# eBOOK_v32.net
KiCad netlist of a schematic drawn in EAGLE
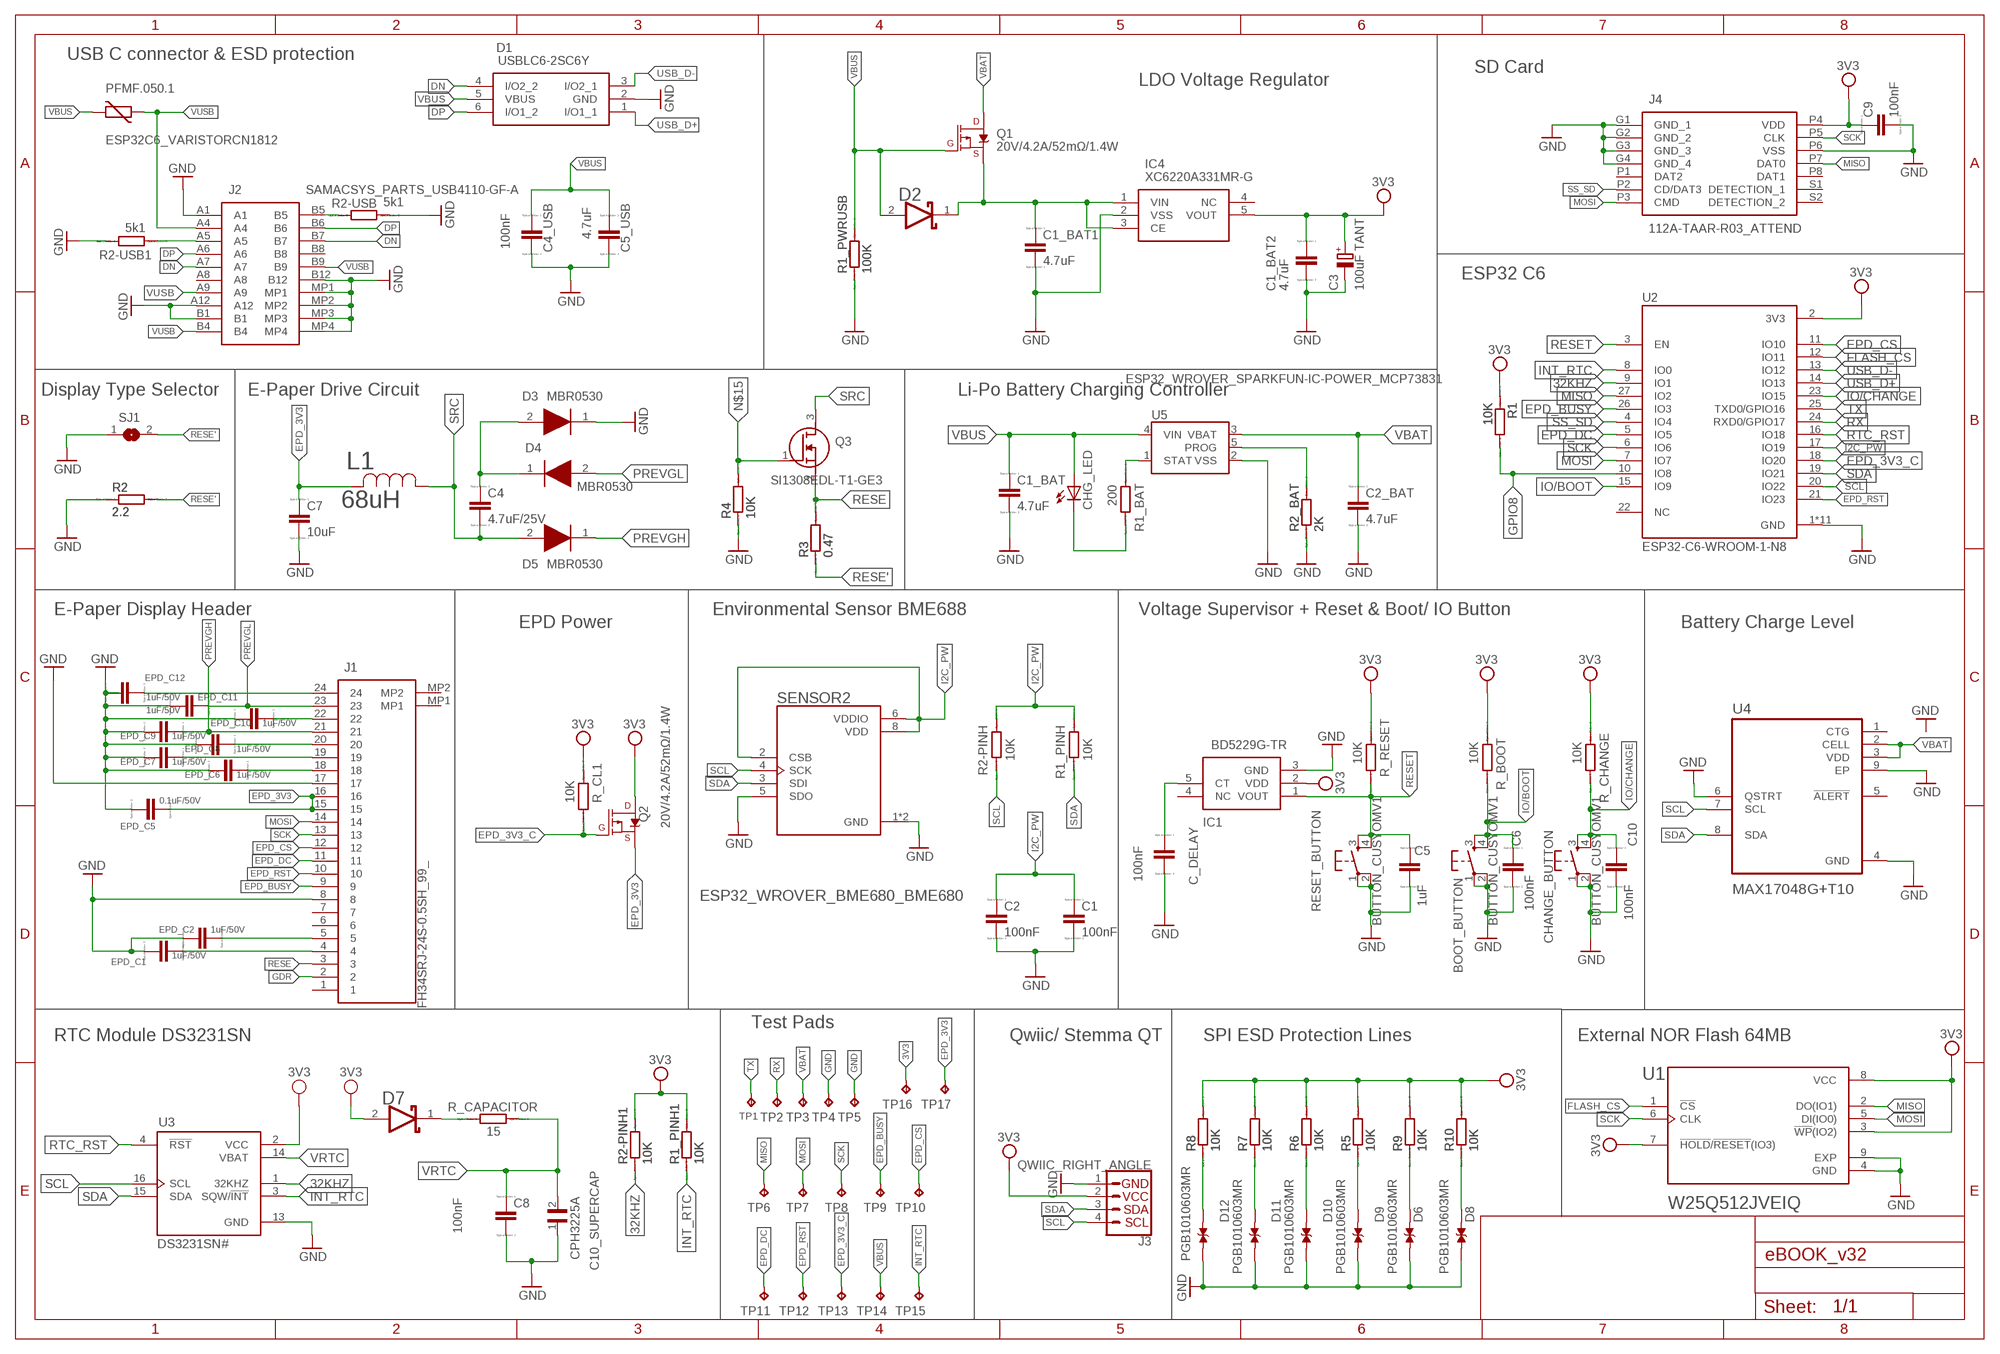
[diagram p0: schematic, sheet 1]

(export (version "E")
  (design (tool "Eeschema 10.0.6"))
  (components
    (comp (ref "BOOT_BUTTON")
      (value "BUTTON_CUSYOMV1")
      (footprint "eagle-import:MYBUTTON")
      (libsource (lib "eagle-import") (part "BUTTON_CUSYOMV1"))
    )
    (comp (ref "C1")
      (value "100nF")
      (footprint "eagle-import:ESP32_WROVER_EAGLE-LTSPICE_C0402")
      (libsource (lib "eagle-import") (part "ESP32_WROVER_EAGLE-LTSPICE_CC0402"))
    )
    (comp (ref "C1_BAT")
      (value "4.7uF")
      (footprint "eagle-import:ESP32_WROVER_EAGLE-LTSPICE_C0402")
      (libsource (lib "eagle-import") (part "ESP32_WROVER_EAGLE-LTSPICE_CC0402"))
    )
    (comp (ref "C1_BAT1")
      (value "4.7uF")
      (footprint "eagle-import:ESP32_WROVER_EAGLE-LTSPICE_C0402")
      (libsource (lib "eagle-import") (part "ESP32_WROVER_EAGLE-LTSPICE_CC0402"))
    )
    (comp (ref "C1_BAT2")
      (value "4.7uF")
      (footprint "eagle-import:ESP32_WROVER_EAGLE-LTSPICE_C0402")
      (libsource (lib "eagle-import") (part "ESP32_WROVER_EAGLE-LTSPICE_CC0402"))
    )
    (comp (ref "C2")
      (value "100nF")
      (footprint "eagle-import:ESP32_WROVER_EAGLE-LTSPICE_C0402")
      (libsource (lib "eagle-import") (part "ESP32_WROVER_EAGLE-LTSPICE_CC0402"))
    )
    (comp (ref "C2_BAT")
      (value "4.7uF")
      (footprint "eagle-import:ESP32_WROVER_EAGLE-LTSPICE_C0402")
      (libsource (lib "eagle-import") (part "ESP32_WROVER_EAGLE-LTSPICE_CC0402"))
    )
    (comp (ref "C3")
      (value "100uF TANT")
      (footprint "eagle-import:RCL_CT3528")
      (libsource (lib "eagle-import") (part "RCL_CPOL-EUCT3528"))
    )
    (comp (ref "C4")
      (value "4.7uF/25V")
      (footprint "eagle-import:ESP32_WROVER_EAGLE-LTSPICE_C0402")
      (libsource (lib "eagle-import") (part "ESP32_WROVER_EAGLE-LTSPICE_CC0402"))
    )
    (comp (ref "C4_USB")
      (value "100nF")
      (footprint "eagle-import:ESP32_WROVER_EAGLE-LTSPICE_C0402")
      (libsource (lib "eagle-import") (part "ESP32_WROVER_EAGLE-LTSPICE_CC0402"))
    )
    (comp (ref "C5")
      (value "1uF")
      (footprint "eagle-import:ESP32_WROVER_EAGLE-LTSPICE_C0402")
      (libsource (lib "eagle-import") (part "ESP32_WROVER_EAGLE-LTSPICE_CC0402"))
    )
    (comp (ref "C5_USB")
      (value "4.7uF")
      (footprint "eagle-import:ESP32_WROVER_EAGLE-LTSPICE_C0402")
      (libsource (lib "eagle-import") (part "ESP32_WROVER_EAGLE-LTSPICE_CC0402"))
    )
    (comp (ref "C6")
      (value "100nF")
      (footprint "eagle-import:ESP32_WROVER_EAGLE-LTSPICE_C0402")
      (libsource (lib "eagle-import") (part "ESP32_WROVER_EAGLE-LTSPICE_CC0402"))
    )
    (comp (ref "C7")
      (value "10uF")
      (footprint "eagle-import:ESP32_WROVER_EAGLE-LTSPICE_C0402")
      (libsource (lib "eagle-import") (part "ESP32_WROVER_EAGLE-LTSPICE_CC0402"))
    )
    (comp (ref "C8")
      (value "100nF")
      (footprint "eagle-import:ESP32_WROVER_EAGLE-LTSPICE_C0402")
      (libsource (lib "eagle-import") (part "ESP32_WROVER_EAGLE-LTSPICE_CC0402"))
    )
    (comp (ref "C9")
      (value "100nF")
      (footprint "eagle-import:ESP32_WROVER_EAGLE-LTSPICE_C0402")
      (libsource (lib "eagle-import") (part "ESP32_WROVER_EAGLE-LTSPICE_CC0402"))
    )
    (comp (ref "C10")
      (value "100nF")
      (footprint "eagle-import:ESP32_WROVER_EAGLE-LTSPICE_C0402")
      (libsource (lib "eagle-import") (part "ESP32_WROVER_EAGLE-LTSPICE_CC0402"))
    )
    (comp (ref "C10_SUPERCAP")
      (value "CPH3225A")
      (footprint "eagle-import:CAPCP3225X100N")
      (fields (field (name "MF") "Seiko Instruments"))
      (libsource (lib "eagle-import") (part "CPH3225A"))
    )
    (comp (ref "CHANGE_BUTTON")
      (value "BUTTON_CUSYOMV1")
      (footprint "eagle-import:MYBUTTON")
      (libsource (lib "eagle-import") (part "BUTTON_CUSYOMV1"))
    )
    (comp (ref "CHG_LED")
      (value "ADAFRUIT_LEDCHIP-LED0603")
      (footprint "eagle-import:ADAFRUIT_CHIP-LED0603")
      (libsource (lib "eagle-import") (part "ADAFRUIT_LEDCHIP-LED0603"))
    )
    (comp (ref "C_DELAY")
      (value "100nF")
      (footprint "eagle-import:ESP32_WROVER_EAGLE-LTSPICE_C0402")
      (libsource (lib "eagle-import") (part "ESP32_WROVER_EAGLE-LTSPICE_CC0402"))
    )
    (comp (ref "D1")
      (value "USBLC6-2SC6Y")
      (footprint "eagle-import:SOT95P280X145-6N")
      (fields (field (name "MF") "STMicroelectronics"))
      (libsource (lib "eagle-import") (part "USBLC6-2SC6Y"))
    )
    (comp (ref "D2")
      (value "ESP32_WROVER_AVX---SD0805S020S1R0_AVX_SD0805S020S1R0_0_0AVX_SD0805S020S1R0_0_0")
      (footprint "eagle-import:ESP32_WROVER_AVX---SD0805S020S1R0_AVX_SD0805S020S1R0_0")
      (fields
        (field (name "DIGIKEY_PART_NUMBER") "478-7800-1-ND")
        (field (name "MF") "AVX")
        (field (name "MOUSER_PART_NUMBER") "581-SD0805S020S1R0")
      )
      (libsource (lib "eagle-import") (part "ESP32_WROVER_AVX---SD0805S020S1R0_AVX_SD0805S020S1R0_0_0AVX_SD0805S020S1R0_0_0"))
    )
    (comp (ref "D3")
      (value "MBR0530")
      (footprint "eagle-import:SOD3716X135N")
      (fields (field (name "MF") "ON Semiconductor"))
      (libsource (lib "eagle-import") (part "MBR0530"))
    )
    (comp (ref "D4")
      (value "MBR0530")
      (footprint "eagle-import:SOD3716X135N")
      (fields (field (name "MF") "ON Semiconductor"))
      (libsource (lib "eagle-import") (part "MBR0530"))
    )
    (comp (ref "D5")
      (value "MBR0530")
      (footprint "eagle-import:SOD3716X135N")
      (fields (field (name "MF") "ON Semiconductor"))
      (libsource (lib "eagle-import") (part "MBR0530"))
    )
    (comp (ref "D6")
      (value "PGB1010603MR")
      (footprint "eagle-import:DIOC1608X36N")
      (fields (field (name "MF") "Littelfuse Inc."))
      (libsource (lib "eagle-import") (part "PGB1010603MR"))
    )
    (comp (ref "D7")
      (value "ESP32_WROVER_AVX---SD0805S020S1R0_AVX_SD0805S020S1R0_0_0AVX_SD0805S020S1R0_0_0")
      (footprint "eagle-import:ESP32_WROVER_AVX---SD0805S020S1R0_AVX_SD0805S020S1R0_0")
      (fields
        (field (name "DIGIKEY_PART_NUMBER") "478-7800-1-ND")
        (field (name "MF") "AVX")
        (field (name "MOUSER_PART_NUMBER") "581-SD0805S020S1R0")
      )
      (libsource (lib "eagle-import") (part "ESP32_WROVER_AVX---SD0805S020S1R0_AVX_SD0805S020S1R0_0_0AVX_SD0805S020S1R0_0_0"))
    )
    (comp (ref "D8")
      (value "PGB1010603MR")
      (footprint "eagle-import:DIOC1608X36N")
      (fields (field (name "MF") "Littelfuse Inc."))
      (libsource (lib "eagle-import") (part "PGB1010603MR"))
    )
    (comp (ref "D9")
      (value "PGB1010603MR")
      (footprint "eagle-import:DIOC1608X36N")
      (fields (field (name "MF") "Littelfuse Inc."))
      (libsource (lib "eagle-import") (part "PGB1010603MR"))
    )
    (comp (ref "D10")
      (value "PGB1010603MR")
      (footprint "eagle-import:DIOC1608X36N")
      (fields (field (name "MF") "Littelfuse Inc."))
      (libsource (lib "eagle-import") (part "PGB1010603MR"))
    )
    (comp (ref "D11")
      (value "PGB1010603MR")
      (footprint "eagle-import:DIOC1608X36N")
      (fields (field (name "MF") "Littelfuse Inc."))
      (libsource (lib "eagle-import") (part "PGB1010603MR"))
    )
    (comp (ref "D12")
      (value "PGB1010603MR")
      (footprint "eagle-import:DIOC1608X36N")
      (fields (field (name "MF") "Littelfuse Inc."))
      (libsource (lib "eagle-import") (part "PGB1010603MR"))
    )
    (comp (ref "EPD_C1")
      (value "1uF/50V")
      (footprint "eagle-import:ESP32_WROVER_EAGLE-LTSPICE_C0402")
      (libsource (lib "eagle-import") (part "ESP32_WROVER_EAGLE-LTSPICE_CC0402"))
    )
    (comp (ref "EPD_C2")
      (value "1uF/50V")
      (footprint "eagle-import:ESP32_WROVER_EAGLE-LTSPICE_C0402")
      (libsource (lib "eagle-import") (part "ESP32_WROVER_EAGLE-LTSPICE_CC0402"))
    )
    (comp (ref "EPD_C5")
      (value "0.1uF/50V")
      (footprint "eagle-import:ESP32_WROVER_EAGLE-LTSPICE_C0402")
      (libsource (lib "eagle-import") (part "ESP32_WROVER_EAGLE-LTSPICE_CC0402"))
    )
    (comp (ref "EPD_C6")
      (value "1uF/50V")
      (footprint "eagle-import:ESP32_WROVER_EAGLE-LTSPICE_C0402")
      (libsource (lib "eagle-import") (part "ESP32_WROVER_EAGLE-LTSPICE_CC0402"))
    )
    (comp (ref "EPD_C7")
      (value "1uF/50V")
      (footprint "eagle-import:ESP32_WROVER_EAGLE-LTSPICE_C0402")
      (libsource (lib "eagle-import") (part "ESP32_WROVER_EAGLE-LTSPICE_CC0402"))
    )
    (comp (ref "EPD_C8")
      (value "1uF/50V")
      (footprint "eagle-import:ESP32_WROVER_EAGLE-LTSPICE_C0402")
      (libsource (lib "eagle-import") (part "ESP32_WROVER_EAGLE-LTSPICE_CC0402"))
    )
    (comp (ref "EPD_C9")
      (value "1uF/50V")
      (footprint "eagle-import:ESP32_WROVER_EAGLE-LTSPICE_C0402")
      (libsource (lib "eagle-import") (part "ESP32_WROVER_EAGLE-LTSPICE_CC0402"))
    )
    (comp (ref "EPD_C10")
      (value "1uF/50V")
      (footprint "eagle-import:ESP32_WROVER_EAGLE-LTSPICE_C0402")
      (libsource (lib "eagle-import") (part "ESP32_WROVER_EAGLE-LTSPICE_CC0402"))
    )
    (comp (ref "EPD_C11")
      (value "1uF/50V")
      (footprint "eagle-import:ESP32_WROVER_EAGLE-LTSPICE_C0402")
      (libsource (lib "eagle-import") (part "ESP32_WROVER_EAGLE-LTSPICE_CC0402"))
    )
    (comp (ref "EPD_C12")
      (value "1uF/50V")
      (footprint "eagle-import:ESP32_WROVER_EAGLE-LTSPICE_C0402")
      (libsource (lib "eagle-import") (part "ESP32_WROVER_EAGLE-LTSPICE_CC0402"))
    )
    (comp (ref "IC1")
      (value "BD5229G-TR")
      (footprint "eagle-import:SOT95P280X125-5N")
      (fields (field (name "MOUSER_PART_NUMBER") "755-BD5229G-TR"))
      (libsource (lib "eagle-import") (part "BD5229G-TR"))
    )
    (comp (ref "IC4")
      (value "XC6220A331MR-G")
      (footprint "eagle-import:SOT95P280X120-5N")
      (fields (field (name "MOUSER_PART_NUMBER") "865-XC6220A331MR-G"))
      (libsource (lib "eagle-import") (part "XC6220A331MR-G"))
    )
    (comp (ref "J1")
      (value "FH34SRJ-24S-0.5SH_99_")
      (footprint "eagle-import:FH34SRJ24S05SH99")
      (fields
        (field (name "MANUFACTURER_PART_NUMBER") "FH34SRJ-24S-0.5SH(99)")
        (field (name "MOUSER_PART_NUMBER") "798-FH34SRJ24S05SH99")
      )
      (libsource (lib "eagle-import") (part "FH34SRJ-24S-0.5SH_99_"))
    )
    (comp (ref "J2")
      (value "SAMACSYS_PARTS_USB4110-GF-A")
      (footprint "eagle-import:SAMACSYS_PARTS_USB4110GFA")
      (fields
        (field (name "MANUFACTURER_PART_NUMBER") "USB4110-GF-A")
        (field (name "MOUSER_PART_NUMBER") "640-USB4110-GF-A")
      )
      (libsource (lib "eagle-import") (part "SAMACSYS_PARTS_USB4110-GF-A"))
    )
    (comp (ref "J3")
      (value "QWIIC_RIGHT_ANGLE")
      (footprint "eagle-import:JST04_1MM_RA")
      (libsource (lib "eagle-import") (part "QWIIC_CONNECTORJS-1MM"))
    )
    (comp (ref "J4")
      (value "112A-TAAR-R03_ATTEND")
      (footprint "eagle-import:112ATAARR03ATTEND")
      (fields (field (name "MANUFACTURER_PART_NUMBER") "112A-TAAR-R03 ATTEND"))
      (libsource (lib "eagle-import") (part "112A-TAAR-R03_ATTEND"))
    )
    (comp (ref "L1")
      (value "68uH")
      (footprint "eagle-import:IND_4828-WE-TPC_WRE")
      (fields
        (field (name "MANUFACTURER_PART_NUMBER") "744043680")
        (field (name "COPYRIGHT") "Copyright (C) 2024 Ultra Librarian. All rights reserved.")
      )
      (libsource (lib "eagle-import") (part "744043680IND_4828-WE-TPC_WRE"))
    )
    (comp (ref "PFMF.050.1")
      (value "ESP32C6_VARISTORCN1812")
      (footprint "eagle-import:ESP32C6_VARISTOR_CT_CN1812")
      (libsource (lib "eagle-import") (part "ESP32C6_VARISTORCN1812"))
    )
    (comp (ref "Q1")
      (value "20V/4.2A/52mΩ/1.4W")
      (footprint "eagle-import:ESP32_WROVER_SPARKFUN-DISCRETESEMI_SOT23-3")
      (libsource (lib "eagle-import") (part "ESP32_WROVER_SPARKFUN-DISCRETESEMI_MOSFET_PCH-DMG2305UX-7"))
    )
    (comp (ref "Q2")
      (value "20V/4.2A/52mΩ/1.4W")
      (footprint "eagle-import:ESP32_WROVER_SPARKFUN-DISCRETESEMI_SOT23-3")
      (libsource (lib "eagle-import") (part "ESP32_WROVER_SPARKFUN-DISCRETESEMI_MOSFET_PCH-DMG2305UX-7"))
    )
    (comp (ref "Q3")
      (value "SI1308EDL-T1-GE3")
      (footprint "eagle-import:SOT65P210X110-3N")
      (fields (field (name "MF") "Vishay Siliconix"))
      (libsource (lib "eagle-import") (part "SI1308EDL-T1-GE3"))
    )
    (comp (ref "R1")
      (value "10K")
      (footprint "eagle-import:ESP32_WROVER_EAGLE-LTSPICE_R0402")
      (libsource (lib "eagle-import") (part "ESP32_WROVER_EAGLE-LTSPICE_RR0402"))
    )
    (comp (ref "R1_BAT")
      (value "200")
      (footprint "eagle-import:ESP32_WROVER_EAGLE-LTSPICE_R0402")
      (libsource (lib "eagle-import") (part "ESP32_WROVER_EAGLE-LTSPICE_RR0402"))
    )
    (comp (ref "R1_PINH")
      (value "10K")
      (footprint "eagle-import:ESP32_WROVER_EAGLE-LTSPICE_R0402")
      (libsource (lib "eagle-import") (part "ESP32_WROVER_EAGLE-LTSPICE_RR0402"))
    )
    (comp (ref "R1_PINH1")
      (value "10K")
      (footprint "eagle-import:ESP32_WROVER_EAGLE-LTSPICE_R0402")
      (libsource (lib "eagle-import") (part "ESP32_WROVER_EAGLE-LTSPICE_RR0402"))
    )
    (comp (ref "R1_PWRUSB")
      (value "100K")
      (footprint "eagle-import:ESP32_WROVER_EAGLE-LTSPICE_R0402")
      (libsource (lib "eagle-import") (part "ESP32_WROVER_EAGLE-LTSPICE_RR0402"))
    )
    (comp (ref "R2")
      (value "2.2")
      (footprint "eagle-import:ESP32_WROVER_EAGLE-LTSPICE_R0402")
      (libsource (lib "eagle-import") (part "ESP32_WROVER_EAGLE-LTSPICE_RR0402"))
    )
    (comp (ref "R2-PINH")
      (value "10K")
      (footprint "eagle-import:ESP32_WROVER_EAGLE-LTSPICE_R0402")
      (libsource (lib "eagle-import") (part "ESP32_WROVER_EAGLE-LTSPICE_RR0402"))
    )
    (comp (ref "R2-PINH1")
      (value "10K")
      (footprint "eagle-import:ESP32_WROVER_EAGLE-LTSPICE_R0402")
      (libsource (lib "eagle-import") (part "ESP32_WROVER_EAGLE-LTSPICE_RR0402"))
    )
    (comp (ref "R2-USB")
      (value "5k1")
      (footprint "eagle-import:ESP32_WROVER_EAGLE-LTSPICE_R0402")
      (libsource (lib "eagle-import") (part "ESP32_WROVER_EAGLE-LTSPICE_RR0402"))
    )
    (comp (ref "R2-USB1")
      (value "5k1")
      (footprint "eagle-import:ESP32_WROVER_EAGLE-LTSPICE_R0402")
      (libsource (lib "eagle-import") (part "ESP32_WROVER_EAGLE-LTSPICE_RR0402"))
    )
    (comp (ref "R2_BAT")
      (value "2K")
      (footprint "eagle-import:ESP32_WROVER_EAGLE-LTSPICE_R0402")
      (libsource (lib "eagle-import") (part "ESP32_WROVER_EAGLE-LTSPICE_RR0402"))
    )
    (comp (ref "R3")
      (value "0.47")
      (footprint "eagle-import:ESP32_WROVER_EAGLE-LTSPICE_R0402")
      (libsource (lib "eagle-import") (part "ESP32_WROVER_EAGLE-LTSPICE_RR0402"))
    )
    (comp (ref "R4")
      (value "10K")
      (footprint "eagle-import:ESP32_WROVER_EAGLE-LTSPICE_R0402")
      (libsource (lib "eagle-import") (part "ESP32_WROVER_EAGLE-LTSPICE_RR0402"))
    )
    (comp (ref "R5")
      (value "10K")
      (footprint "eagle-import:ESP32_WROVER_EAGLE-LTSPICE_R0402")
      (libsource (lib "eagle-import") (part "ESP32_WROVER_EAGLE-LTSPICE_RR0402"))
    )
    (comp (ref "R6")
      (value "10K")
      (footprint "eagle-import:ESP32_WROVER_EAGLE-LTSPICE_R0402")
      (libsource (lib "eagle-import") (part "ESP32_WROVER_EAGLE-LTSPICE_RR0402"))
    )
    (comp (ref "R7")
      (value "10K")
      (footprint "eagle-import:ESP32_WROVER_EAGLE-LTSPICE_R0402")
      (libsource (lib "eagle-import") (part "ESP32_WROVER_EAGLE-LTSPICE_RR0402"))
    )
    (comp (ref "R8")
      (value "10K")
      (footprint "eagle-import:ESP32_WROVER_EAGLE-LTSPICE_R0402")
      (libsource (lib "eagle-import") (part "ESP32_WROVER_EAGLE-LTSPICE_RR0402"))
    )
    (comp (ref "R9")
      (value "10K")
      (footprint "eagle-import:ESP32_WROVER_EAGLE-LTSPICE_R0402")
      (libsource (lib "eagle-import") (part "ESP32_WROVER_EAGLE-LTSPICE_RR0402"))
    )
    (comp (ref "R10")
      (value "10K")
      (footprint "eagle-import:ESP32_WROVER_EAGLE-LTSPICE_R0402")
      (libsource (lib "eagle-import") (part "ESP32_WROVER_EAGLE-LTSPICE_RR0402"))
    )
    (comp (ref "RESET_BUTTON")
      (value "BUTTON_CUSYOMV1")
      (footprint "eagle-import:MYBUTTON")
      (libsource (lib "eagle-import") (part "BUTTON_CUSYOMV1"))
    )
    (comp (ref "R_BOOT")
      (value "10K")
      (footprint "eagle-import:ESP32_WROVER_EAGLE-LTSPICE_R0402")
      (libsource (lib "eagle-import") (part "ESP32_WROVER_EAGLE-LTSPICE_RR0402"))
    )
    (comp (ref "R_CAPACITOR")
      (value "15")
      (footprint "eagle-import:ESP32_WROVER_EAGLE-LTSPICE_R0402")
      (libsource (lib "eagle-import") (part "ESP32_WROVER_EAGLE-LTSPICE_RR0402"))
    )
    (comp (ref "R_CHANGE")
      (value "10K")
      (footprint "eagle-import:ESP32_WROVER_EAGLE-LTSPICE_R0402")
      (libsource (lib "eagle-import") (part "ESP32_WROVER_EAGLE-LTSPICE_RR0402"))
    )
    (comp (ref "R_CL1")
      (value "10K")
      (footprint "eagle-import:ESP32_WROVER_EAGLE-LTSPICE_R0402")
      (libsource (lib "eagle-import") (part "ESP32_WROVER_EAGLE-LTSPICE_RR0402"))
    )
    (comp (ref "R_RESET")
      (value "10K")
      (footprint "eagle-import:ESP32_WROVER_EAGLE-LTSPICE_R0402")
      (libsource (lib "eagle-import") (part "ESP32_WROVER_EAGLE-LTSPICE_RR0402"))
    )
    (comp (ref "SENSOR2")
      (value "ESP32_WROVER_BME680_BME680")
      (footprint "eagle-import:ESP32_WROVER_BME680_PSON80P300X300X100-8N")
      (fields (field (name "MF") "Bosch Sensortec") (field (name "MP") "BME680"))
      (libsource (lib "eagle-import") (part "ESP32_WROVER_BME680_BME680"))
    )
    (comp (ref "SJ1") (value "SJ") (footprint "eagle-import:SJ") (libsource (lib "eagle-import") (part "SJ")))
    (comp (ref "TP1")
      (value "TPTP20R")
      (footprint "eagle-import:TP20R")
      (libsource (lib "eagle-import") (part "TPTP20R"))
    )
    (comp (ref "TP2")
      (value "TPTP20R")
      (footprint "eagle-import:TP20R")
      (libsource (lib "eagle-import") (part "TPTP20R"))
    )
    (comp (ref "TP3")
      (value "TPTP20R")
      (footprint "eagle-import:TP20R")
      (libsource (lib "eagle-import") (part "TPTP20R"))
    )
    (comp (ref "TP4")
      (value "TPTP20R")
      (footprint "eagle-import:TP20R")
      (libsource (lib "eagle-import") (part "TPTP20R"))
    )
    (comp (ref "TP5")
      (value "TPTP20R")
      (footprint "eagle-import:TP20R")
      (libsource (lib "eagle-import") (part "TPTP20R"))
    )
    (comp (ref "TP6")
      (value "TPTP20R")
      (footprint "eagle-import:TP20R")
      (libsource (lib "eagle-import") (part "TPTP20R"))
    )
    (comp (ref "TP7")
      (value "TPTP20R")
      (footprint "eagle-import:TP20R")
      (libsource (lib "eagle-import") (part "TPTP20R"))
    )
    (comp (ref "TP8")
      (value "TPTP20R")
      (footprint "eagle-import:TP20R")
      (libsource (lib "eagle-import") (part "TPTP20R"))
    )
    (comp (ref "TP9")
      (value "TPTP20R")
      (footprint "eagle-import:TP20R")
      (libsource (lib "eagle-import") (part "TPTP20R"))
    )
    (comp (ref "TP10")
      (value "TPTP20R")
      (footprint "eagle-import:TP20R")
      (libsource (lib "eagle-import") (part "TPTP20R"))
    )
    (comp (ref "TP11")
      (value "TPTP20R")
      (footprint "eagle-import:TP20R")
      (libsource (lib "eagle-import") (part "TPTP20R"))
    )
    (comp (ref "TP12")
      (value "TPTP20R")
      (footprint "eagle-import:TP20R")
      (libsource (lib "eagle-import") (part "TPTP20R"))
    )
    (comp (ref "TP13")
      (value "TPTP20R")
      (footprint "eagle-import:TP20R")
      (libsource (lib "eagle-import") (part "TPTP20R"))
    )
    (comp (ref "TP14")
      (value "TPTP20R")
      (footprint "eagle-import:TP20R")
      (libsource (lib "eagle-import") (part "TPTP20R"))
    )
    (comp (ref "TP15")
      (value "TPTP20R")
      (footprint "eagle-import:TP20R")
      (libsource (lib "eagle-import") (part "TPTP20R"))
    )
    (comp (ref "TP16")
      (value "TPTP20R")
      (footprint "eagle-import:TP20R")
      (libsource (lib "eagle-import") (part "TPTP20R"))
    )
    (comp (ref "TP17")
      (value "TPTP20R")
      (footprint "eagle-import:TP20R")
      (libsource (lib "eagle-import") (part "TPTP20R"))
    )
    (comp (ref "U1")
      (value "W25Q512JVEIQ")
      (footprint "eagle-import:SON127P600X800X80-9N")
      (fields (field (name "MF") "Winbond Electronics"))
      (libsource (lib "eagle-import") (part "W25Q512JVEIQ"))
    )
    (comp (ref "U2")
      (value "ESP32-C6-WROOM-1-N8")
      (footprint "eagle-import:XCVR_ESP32-C6-WROOM-1-N8")
      (fields (field (name "MF") "Espressif Systems"))
      (libsource (lib "eagle-import") (part "ESP32-C6-WROOM-1-N8"))
    )
    (comp (ref "U3")
      (value "DS3231SN#")
      (footprint "eagle-import:SOIC127P1032X265-16N")
      (fields (field (name "MF") "Maxim Integrated Products"))
      (libsource (lib "eagle-import") (part "DS3231SN#"))
    )
    (comp (ref "U4")
      (value "MAX17048G+T10")
      (footprint "eagle-import:SON50P200X200X80-9N")
      (fields (field (name "MF") "Analog Devices"))
      (libsource (lib "eagle-import") (part "MAX17048G+T10"))
    )
    (comp (ref "U5")
      (value "ESP32_WROVER_SPARKFUN-IC-POWER_MCP73831")
      (footprint "eagle-import:ESP32_WROVER_SPARKFUN-IC-POWER_SOT23-5")
      (libsource (lib "eagle-import") (part "ESP32_WROVER_SPARKFUN-IC-POWER_MCP73831"))
    )
  )
  (nets
    (net (code "1") (name "/CTG") (class "Default")
      (node (ref "U4") (pin "1") (pinfunction "CTG_1") (pintype "power_in"))
    )
    (net (code "2") (name "3V3") (class "Default")
      (node (ref "C1_BAT2") (pin "1") (pinfunction "1_1") (pintype "passive"))
      (node (ref "C3") (pin "+") (pinfunction "+_+") (pintype "passive"))
      (node (ref "C9") (pin "1") (pinfunction "1_1") (pintype "passive"))
      (node (ref "D7") (pin "2") (pinfunction "ANODE_2") (pintype "bidirectional"))
      (node (ref "IC1") (pin "2") (pinfunction "VDD_2") (pintype "bidirectional"))
      (node (ref "IC4") (pin "5") (pinfunction "VOUT_5") (pintype "bidirectional"))
      (node (ref "J3") (pin "2") (pinfunction "2_2") (pintype "power_in"))
      (node (ref "J4") (pin "P4") (pinfunction "VDD_P4") (pintype "bidirectional"))
      (node (ref "Q2") (pin "3") (pinfunction "D_3") (pintype "bidirectional"))
      (node (ref "R1") (pin "1") (pinfunction "1_1") (pintype "passive"))
      (node (ref "R10") (pin "2") (pinfunction "2_2") (pintype "passive"))
      (node (ref "R1_PINH1") (pin "2") (pinfunction "2_2") (pintype "passive"))
      (node (ref "R2-PINH1") (pin "2") (pinfunction "2_2") (pintype "passive"))
      (node (ref "R5") (pin "2") (pinfunction "2_2") (pintype "passive"))
      (node (ref "R6") (pin "2") (pinfunction "2_2") (pintype "passive"))
      (node (ref "R7") (pin "2") (pinfunction "2_2") (pintype "passive"))
      (node (ref "R8") (pin "2") (pinfunction "2_2") (pintype "passive"))
      (node (ref "R9") (pin "2") (pinfunction "2_2") (pintype "passive"))
      (node (ref "R_BOOT") (pin "2") (pinfunction "2_2") (pintype "passive"))
      (node (ref "R_CHANGE") (pin "2") (pinfunction "2_2") (pintype "passive"))
      (node (ref "R_CL1") (pin "2") (pinfunction "2_2") (pintype "passive"))
      (node (ref "R_RESET") (pin "2") (pinfunction "2_2") (pintype "passive"))
      (node (ref "TP16") (pin "TP") (pinfunction "TP_TP") (pintype "input"))
      (node (ref "U1") (pin "3") (pinfunction "~{WP}(IO2)_3") (pintype "bidirectional"))
      (node (ref "U1") (pin "7") (pinfunction "~{HOLD}/~{RESET}(IO3)_7") (pintype "bidirectional"))
      (node (ref "U1") (pin "8") (pinfunction "VCC_8") (pintype "power_in"))
      (node (ref "U2") (pin "2") (pinfunction "3V3_2") (pintype "power_in"))
      (node (ref "U3") (pin "2") (pinfunction "VCC_2") (pintype "power_in"))
    )
    (net (code "3") (name "32KHZ") (class "Default")
      (node (ref "R2-PINH1") (pin "1") (pinfunction "1_1") (pintype "passive"))
      (node (ref "U2") (pin "9") (pinfunction "IO1_9") (pintype "bidirectional"))
      (node (ref "U3") (pin "1") (pinfunction "32KHZ_1") (pintype "output"))
    )
    (net (code "4") (name "DN") (class "Default")
      (node (ref "D1") (pin "4") (pinfunction "I/O2_2_4") (pintype "bidirectional"))
      (node (ref "J2") (pin "A7") (pinfunction "A7_A7") (pintype "bidirectional"))
      (node (ref "J2") (pin "B7") (pinfunction "B7_B7") (pintype "bidirectional"))
    )
    (net (code "5") (name "DP") (class "Default")
      (node (ref "D1") (pin "6") (pinfunction "I/O1_2_6") (pintype "bidirectional"))
      (node (ref "J2") (pin "A6") (pinfunction "A6_A6") (pintype "bidirectional"))
      (node (ref "J2") (pin "B6") (pinfunction "B6_B6") (pintype "bidirectional"))
    )
    (net (code "6") (name "EPD_3V3") (class "Default")
      (node (ref "C7") (pin "1") (pinfunction "1_1") (pintype "passive"))
      (node (ref "EPD_C5") (pin "1") (pinfunction "1_1") (pintype "passive"))
      (node (ref "J1") (pin "15") (pinfunction "15_15") (pintype "bidirectional"))
      (node (ref "J1") (pin "16") (pinfunction "16_16") (pintype "bidirectional"))
      (node (ref "L1") (pin "2") (pinfunction "2_2") (pintype "passive"))
      (node (ref "Q2") (pin "2") (pinfunction "S_2") (pintype "bidirectional"))
      (node (ref "TP17") (pin "TP") (pinfunction "TP_TP") (pintype "input"))
    )
    (net (code "7") (name "EPD_3V3_C") (class "Default")
      (node (ref "Q2") (pin "1") (pinfunction "G_1") (pintype "bidirectional"))
      (node (ref "R_CL1") (pin "1") (pinfunction "1_1") (pintype "passive"))
      (node (ref "TP13") (pin "TP") (pinfunction "TP_TP") (pintype "input"))
      (node (ref "U2") (pin "18") (pinfunction "IO20_18") (pintype "bidirectional"))
    )
    (net (code "8") (name "EPD_BUSY") (class "Default")
      (node (ref "J1") (pin "9") (pinfunction "9_9") (pintype "bidirectional"))
      (node (ref "TP9") (pin "TP") (pinfunction "TP_TP") (pintype "input"))
      (node (ref "U2") (pin "26") (pinfunction "IO3_26") (pintype "bidirectional"))
    )
    (net (code "9") (name "EPD_CS") (class "Default")
      (node (ref "J1") (pin "12") (pinfunction "12_12") (pintype "bidirectional"))
      (node (ref "TP10") (pin "TP") (pinfunction "TP_TP") (pintype "input"))
      (node (ref "U2") (pin "11") (pinfunction "IO10_11") (pintype "bidirectional"))
    )
    (net (code "10") (name "EPD_DC") (class "Default")
      (node (ref "J1") (pin "11") (pinfunction "11_11") (pintype "bidirectional"))
      (node (ref "TP11") (pin "TP") (pinfunction "TP_TP") (pintype "input"))
      (node (ref "U2") (pin "5") (pinfunction "IO5_5") (pintype "bidirectional"))
    )
    (net (code "11") (name "EPD_RST") (class "Default")
      (node (ref "J1") (pin "10") (pinfunction "10_10") (pintype "bidirectional"))
      (node (ref "TP12") (pin "TP") (pinfunction "TP_TP") (pintype "input"))
      (node (ref "U2") (pin "21") (pinfunction "IO23_21") (pintype "bidirectional"))
    )
    (net (code "12") (name "FLASH_CS") (class "Default")
      (node (ref "U1") (pin "1") (pinfunction "~{CS}_1") (pintype "input"))
      (node (ref "U2") (pin "12") (pinfunction "IO11_12") (pintype "bidirectional"))
    )
    (net (code "13") (name "GDR") (class "Default")
      (node (ref "J1") (pin "2") (pinfunction "2_2") (pintype "bidirectional"))
    )
    (net (code "14") (name "GND") (class "Default")
      (node (ref "BOOT_BUTTON") (pin "1") (pinfunction "1_1") (pintype "passive"))
      (node (ref "BOOT_BUTTON") (pin "2") (pinfunction "2_2") (pintype "passive"))
      (node (ref "C1") (pin "2") (pinfunction "2_2") (pintype "passive"))
      (node (ref "C10") (pin "2") (pinfunction "2_2") (pintype "passive"))
      (node (ref "C10_SUPERCAP") (pin "1") (pinfunction "1_1") (pintype "passive"))
      (node (ref "C1_BAT") (pin "2") (pinfunction "2_2") (pintype "passive"))
      (node (ref "C1_BAT1") (pin "2") (pinfunction "2_2") (pintype "passive"))
      (node (ref "C1_BAT2") (pin "2") (pinfunction "2_2") (pintype "passive"))
      (node (ref "C2") (pin "2") (pinfunction "2_2") (pintype "passive"))
      (node (ref "C2_BAT") (pin "2") (pinfunction "2_2") (pintype "passive"))
      (node (ref "C3") (pin "-") (pinfunction "-_-") (pintype "passive"))
      (node (ref "C4_USB") (pin "2") (pinfunction "2_2") (pintype "passive"))
      (node (ref "C5") (pin "2") (pinfunction "2_2") (pintype "passive"))
      (node (ref "C5_USB") (pin "2") (pinfunction "2_2") (pintype "passive"))
      (node (ref "C6") (pin "2") (pinfunction "2_2") (pintype "passive"))
      (node (ref "C7") (pin "2") (pinfunction "2_2") (pintype "passive"))
      (node (ref "C8") (pin "2") (pinfunction "2_2") (pintype "passive"))
      (node (ref "C9") (pin "2") (pinfunction "2_2") (pintype "passive"))
      (node (ref "CHANGE_BUTTON") (pin "1") (pinfunction "1_1") (pintype "passive"))
      (node (ref "CHANGE_BUTTON") (pin "2") (pinfunction "2_2") (pintype "passive"))
      (node (ref "C_DELAY") (pin "2") (pinfunction "2_2") (pintype "passive"))
      (node (ref "D1") (pin "2") (pinfunction "GND_2") (pintype "bidirectional"))
      (node (ref "D10") (pin "1") (pinfunction "1_1") (pintype "passive"))
      (node (ref "D11") (pin "1") (pinfunction "1_1") (pintype "passive"))
      (node (ref "D12") (pin "1") (pinfunction "1_1") (pintype "passive"))
      (node (ref "D3") (pin "1") (pinfunction "K_1") (pintype "bidirectional"))
      (node (ref "D6") (pin "1") (pinfunction "1_1") (pintype "passive"))
      (node (ref "D8") (pin "1") (pinfunction "1_1") (pintype "passive"))
      (node (ref "D9") (pin "1") (pinfunction "1_1") (pintype "passive"))
      (node (ref "EPD_C1") (pin "2") (pinfunction "2_2") (pintype "passive"))
      (node (ref "EPD_C10") (pin "2") (pinfunction "2_2") (pintype "passive"))
      (node (ref "EPD_C11") (pin "2") (pinfunction "2_2") (pintype "passive"))
      (node (ref "EPD_C12") (pin "2") (pinfunction "2_2") (pintype "passive"))
      (node (ref "EPD_C2") (pin "2") (pinfunction "2_2") (pintype "passive"))
      (node (ref "EPD_C5") (pin "2") (pinfunction "2_2") (pintype "passive"))
      (node (ref "EPD_C6") (pin "2") (pinfunction "2_2") (pintype "passive"))
      (node (ref "EPD_C7") (pin "2") (pinfunction "2_2") (pintype "passive"))
      (node (ref "EPD_C8") (pin "2") (pinfunction "2_2") (pintype "passive"))
      (node (ref "EPD_C9") (pin "2") (pinfunction "2_2") (pintype "passive"))
      (node (ref "IC1") (pin "3") (pinfunction "GND_3") (pintype "bidirectional"))
      (node (ref "IC4") (pin "2") (pinfunction "VSS_2") (pintype "bidirectional"))
      (node (ref "J1") (pin "17") (pinfunction "17_17") (pintype "bidirectional"))
      (node (ref "J1") (pin "8") (pinfunction "8_8") (pintype "bidirectional"))
      (node (ref "J2") (pin "A1") (pinfunction "A1_A1") (pintype "bidirectional"))
      (node (ref "J2") (pin "A12") (pinfunction "A12_A12") (pintype "bidirectional"))
      (node (ref "J2") (pin "B1") (pinfunction "B1_B1") (pintype "bidirectional"))
      (node (ref "J2") (pin "B12") (pinfunction "B12_B12") (pintype "bidirectional"))
      (node (ref "J2") (pin "MP1") (pinfunction "MP1_MP1") (pintype "bidirectional"))
      (node (ref "J2") (pin "MP2") (pinfunction "MP2_MP2") (pintype "bidirectional"))
      (node (ref "J2") (pin "MP3") (pinfunction "MP3_MP3") (pintype "bidirectional"))
      (node (ref "J2") (pin "MP4") (pinfunction "MP4_MP4") (pintype "bidirectional"))
      (node (ref "J3") (pin "1") (pinfunction "1_1") (pintype "power_in"))
      (node (ref "J4") (pin "G1") (pinfunction "GND_1_G1") (pintype "bidirectional"))
      (node (ref "J4") (pin "G2") (pinfunction "GND_2_G2") (pintype "bidirectional"))
      (node (ref "J4") (pin "G3") (pinfunction "GND_3_G3") (pintype "bidirectional"))
      (node (ref "J4") (pin "G4") (pinfunction "GND_4_G4") (pintype "bidirectional"))
      (node (ref "J4") (pin "P6") (pinfunction "VSS_P6") (pintype "bidirectional"))
      (node (ref "R1_PWRUSB") (pin "1") (pinfunction "1_1") (pintype "passive"))
      (node (ref "R2") (pin "1") (pinfunction "1_1") (pintype "passive"))
      (node (ref "R2-USB") (pin "2") (pinfunction "2_2") (pintype "passive"))
      (node (ref "R2-USB1") (pin "1") (pinfunction "1_1") (pintype "passive"))
      (node (ref "R2_BAT") (pin "1") (pinfunction "1_1") (pintype "passive"))
      (node (ref "R4") (pin "1") (pinfunction "1_1") (pintype "passive"))
      (node (ref "RESET_BUTTON") (pin "1") (pinfunction "1_1") (pintype "passive"))
      (node (ref "RESET_BUTTON") (pin "2") (pinfunction "2_2") (pintype "passive"))
      (node (ref "SENSOR2") (pin "1") (pinfunction "GND_1") (pintype "power_in"))
      (node (ref "SENSOR2") (pin "5") (pinfunction "SDO_5") (pintype "bidirectional"))
      (node (ref "SENSOR2") (pin "7") (pinfunction "GND_7") (pintype "power_in"))
      (node (ref "SJ1") (pin "1") (pinfunction "1_1") (pintype "passive"))
      (node (ref "TP4") (pin "TP") (pinfunction "TP_TP") (pintype "input"))
      (node (ref "TP5") (pin "TP") (pinfunction "TP_TP") (pintype "input"))
      (node (ref "U1") (pin "4") (pinfunction "GND_4") (pintype "power_in"))
      (node (ref "U1") (pin "9") (pinfunction "EXP_9") (pintype "passive"))
      (node (ref "U2") (pin "1") (pinfunction "GND_1") (pintype "power_in"))
      (node (ref "U2") (pin "28") (pinfunction "GND_28") (pintype "power_in"))
      (node (ref "U2") (pin "29_1") (pinfunction "GND_29_1") (pintype "power_in"))
      (node (ref "U2") (pin "29_2") (pinfunction "GND_29_2") (pintype "power_in"))
      (node (ref "U2") (pin "29_3") (pinfunction "GND_29_3") (pintype "power_in"))
      (node (ref "U2") (pin "29_4") (pinfunction "GND_29_4") (pintype "power_in"))
      (node (ref "U2") (pin "29_5") (pinfunction "GND_29_5") (pintype "power_in"))
      (node (ref "U2") (pin "29_6") (pinfunction "GND_29_6") (pintype "power_in"))
      (node (ref "U2") (pin "29_7") (pinfunction "GND_29_7") (pintype "power_in"))
      (node (ref "U2") (pin "29_8") (pinfunction "GND_29_8") (pintype "power_in"))
      (node (ref "U2") (pin "29_9") (pinfunction "GND_29_9") (pintype "power_in"))
      (node (ref "U3") (pin "13") (pinfunction "GND_13") (pintype "power_in"))
      (node (ref "U4") (pin "4") (pinfunction "GND_4") (pintype "power_in"))
      (node (ref "U4") (pin "6") (pinfunction "QSTRT_6") (pintype "input"))
      (node (ref "U4") (pin "9") (pinfunction "EP_9") (pintype "power_in"))
      (node (ref "U5") (pin "2") (pinfunction "VSS_2") (pintype "power_in"))
    )
    (net (code "15") (name "GPIO8") (class "Default")
      (node (ref "R1") (pin "2") (pinfunction "2_2") (pintype "passive"))
      (node (ref "U2") (pin "10") (pinfunction "IO8_10") (pintype "bidirectional"))
    )
    (net (code "16") (name "I2C_PW") (class "Default")
      (node (ref "C1") (pin "1") (pinfunction "1_1") (pintype "passive"))
      (node (ref "C2") (pin "1") (pinfunction "1_1") (pintype "passive"))
      (node (ref "R1_PINH") (pin "1") (pinfunction "1_1") (pintype "passive"))
      (node (ref "R2-PINH") (pin "1") (pinfunction "1_1") (pintype "passive"))
      (node (ref "SENSOR2") (pin "2") (pinfunction "CSB_2") (pintype "input"))
      (node (ref "SENSOR2") (pin "6") (pinfunction "VDDIO_6") (pintype "power_in"))
      (node (ref "SENSOR2") (pin "8") (pinfunction "VDD_8") (pintype "power_in"))
      (node (ref "U2") (pin "17") (pinfunction "IO19_17") (pintype "bidirectional"))
    )
    (net (code "17") (name "INT_RTC") (class "Default")
      (node (ref "R1_PINH1") (pin "1") (pinfunction "1_1") (pintype "passive"))
      (node (ref "TP15") (pin "TP") (pinfunction "TP_TP") (pintype "input"))
      (node (ref "U2") (pin "8") (pinfunction "IO0_8") (pintype "bidirectional"))
      (node (ref "U3") (pin "3") (pinfunction "SQW/~{INT}_3") (pintype "output"))
    )
    (net (code "18") (name "IO{slash}BOOT") (class "Default")
      (node (ref "BOOT_BUTTON") (pin "3") (pinfunction "3_3") (pintype "passive"))
      (node (ref "BOOT_BUTTON") (pin "4") (pinfunction "4_4") (pintype "passive"))
      (node (ref "C6") (pin "1") (pinfunction "1_1") (pintype "passive"))
      (node (ref "R_BOOT") (pin "1") (pinfunction "1_1") (pintype "passive"))
      (node (ref "U2") (pin "15") (pinfunction "IO9_15") (pintype "bidirectional"))
    )
    (net (code "19") (name "IO{slash}CHANGE") (class "Default")
      (node (ref "C10") (pin "1") (pinfunction "1_1") (pintype "passive"))
      (node (ref "CHANGE_BUTTON") (pin "3") (pinfunction "3_3") (pintype "passive"))
      (node (ref "CHANGE_BUTTON") (pin "4") (pinfunction "4_4") (pintype "passive"))
      (node (ref "R_CHANGE") (pin "1") (pinfunction "1_1") (pintype "passive"))
      (node (ref "U2") (pin "23") (pinfunction "IO15_23") (pintype "bidirectional"))
    )
    (net (code "20") (name "MISO") (class "Default")
      (node (ref "J4") (pin "P7") (pinfunction "DAT0_P7") (pintype "bidirectional"))
      (node (ref "TP6") (pin "TP") (pinfunction "TP_TP") (pintype "input"))
      (node (ref "U1") (pin "2") (pinfunction "DO(IO1)_2") (pintype "bidirectional"))
      (node (ref "U2") (pin "27") (pinfunction "IO2_27") (pintype "bidirectional"))
    )
    (net (code "21") (name "MOSI") (class "Default")
      (node (ref "J1") (pin "14") (pinfunction "14_14") (pintype "bidirectional"))
      (node (ref "J4") (pin "P3") (pinfunction "CMD_P3") (pintype "bidirectional"))
      (node (ref "TP7") (pin "TP") (pinfunction "TP_TP") (pintype "input"))
      (node (ref "U1") (pin "5") (pinfunction "DI(IO0)_5") (pintype "bidirectional"))
      (node (ref "U2") (pin "7") (pinfunction "IO7_7") (pintype "bidirectional"))
    )
    (net (code "22") (name "N$15") (class "Default")
      (node (ref "Q3") (pin "1") (pinfunction "G_1") (pintype "bidirectional"))
      (node (ref "R4") (pin "2") (pinfunction "2_2") (pintype "passive"))
    )
    (net (code "23") (name "Net-(CHG_LED-PadC)") (class "Default")
      (node (ref "CHG_LED") (pin "C") (pinfunction "C_C") (pintype "passive"))
      (node (ref "R1_BAT") (pin "1") (pinfunction "1_1") (pintype "passive"))
    )
    (net (code "24") (name "Net-(D2-CATHODE)") (class "Default")
      (node (ref "C1_BAT1") (pin "1") (pinfunction "1_1") (pintype "passive"))
      (node (ref "D2") (pin "1") (pinfunction "CATHODE_1") (pintype "bidirectional"))
      (node (ref "IC4") (pin "1") (pinfunction "VIN_1") (pintype "bidirectional"))
      (node (ref "IC4") (pin "3") (pinfunction "CE_3") (pintype "bidirectional"))
      (node (ref "Q1") (pin "2") (pinfunction "S_2") (pintype "bidirectional"))
    )
    (net (code "25") (name "Net-(D3-A)") (class "Default")
      (node (ref "C4") (pin "1") (pinfunction "1_1") (pintype "passive"))
      (node (ref "D3") (pin "2") (pinfunction "A_2") (pintype "bidirectional"))
      (node (ref "D4") (pin "1") (pinfunction "K_1") (pintype "bidirectional"))
    )
    (net (code "26") (name "Net-(D6-Pad2)") (class "Default")
      (node (ref "D6") (pin "2") (pinfunction "2_2") (pintype "passive"))
      (node (ref "R9") (pin "1") (pinfunction "1_1") (pintype "passive"))
    )
    (net (code "27") (name "Net-(D7-CATHODE)") (class "Default")
      (node (ref "D7") (pin "1") (pinfunction "CATHODE_1") (pintype "bidirectional"))
      (node (ref "R_CAPACITOR") (pin "1") (pinfunction "1_1") (pintype "passive"))
    )
    (net (code "28") (name "Net-(D8-Pad2)") (class "Default")
      (node (ref "D8") (pin "2") (pinfunction "2_2") (pintype "passive"))
      (node (ref "R10") (pin "1") (pinfunction "1_1") (pintype "passive"))
    )
    (net (code "29") (name "Net-(D9-Pad2)") (class "Default")
      (node (ref "D9") (pin "2") (pinfunction "2_2") (pintype "passive"))
      (node (ref "R5") (pin "1") (pinfunction "1_1") (pintype "passive"))
    )
    (net (code "30") (name "Net-(D10-Pad2)") (class "Default")
      (node (ref "D10") (pin "2") (pinfunction "2_2") (pintype "passive"))
      (node (ref "R6") (pin "1") (pinfunction "1_1") (pintype "passive"))
    )
    (net (code "31") (name "Net-(D11-Pad2)") (class "Default")
      (node (ref "D11") (pin "2") (pinfunction "2_2") (pintype "passive"))
      (node (ref "R7") (pin "1") (pinfunction "1_1") (pintype "passive"))
    )
    (net (code "32") (name "Net-(D12-Pad2)") (class "Default")
      (node (ref "D12") (pin "2") (pinfunction "2_2") (pintype "passive"))
      (node (ref "R8") (pin "1") (pinfunction "1_1") (pintype "passive"))
    )
    (net (code "33") (name "Net-(EPD_C1-Pad1)") (class "Default")
      (node (ref "EPD_C1") (pin "1") (pinfunction "1_1") (pintype "passive"))
      (node (ref "J1") (pin "4") (pinfunction "4_4") (pintype "bidirectional"))
    )
    (net (code "34") (name "Net-(EPD_C2-Pad1)") (class "Default")
      (node (ref "EPD_C2") (pin "1") (pinfunction "1_1") (pintype "passive"))
      (node (ref "J1") (pin "5") (pinfunction "5_5") (pintype "bidirectional"))
    )
    (net (code "35") (name "Net-(EPD_C6-Pad1)") (class "Default")
      (node (ref "EPD_C6") (pin "1") (pinfunction "1_1") (pintype "passive"))
      (node (ref "J1") (pin "18") (pinfunction "18_18") (pintype "bidirectional"))
    )
    (net (code "36") (name "Net-(EPD_C7-Pad1)") (class "Default")
      (node (ref "EPD_C7") (pin "1") (pinfunction "1_1") (pintype "passive"))
      (node (ref "J1") (pin "19") (pinfunction "19_19") (pintype "bidirectional"))
    )
    (net (code "37") (name "Net-(EPD_C8-Pad1)") (class "Default")
      (node (ref "EPD_C8") (pin "1") (pinfunction "1_1") (pintype "passive"))
      (node (ref "J1") (pin "20") (pinfunction "20_20") (pintype "bidirectional"))
    )
    (net (code "38") (name "Net-(EPD_C10-Pad1)") (class "Default")
      (node (ref "EPD_C10") (pin "1") (pinfunction "1_1") (pintype "passive"))
      (node (ref "J1") (pin "22") (pinfunction "22_22") (pintype "bidirectional"))
    )
    (net (code "39") (name "Net-(EPD_C12-Pad1)") (class "Default")
      (node (ref "EPD_C12") (pin "1") (pinfunction "1_1") (pintype "passive"))
      (node (ref "J1") (pin "24") (pinfunction "24_24") (pintype "bidirectional"))
    )
    (net (code "40") (name "Net-(IC1-CT)") (class "Default")
      (node (ref "C_DELAY") (pin "1") (pinfunction "1_1") (pintype "passive"))
      (node (ref "IC1") (pin "5") (pinfunction "CT_5") (pintype "bidirectional"))
    )
    (net (code "41") (name "Net-(J2-PadA5)") (class "Default")
      (node (ref "J2") (pin "A5") (pinfunction "A5_A5") (pintype "bidirectional"))
      (node (ref "R2-USB1") (pin "2") (pinfunction "2_2") (pintype "passive"))
    )
    (net (code "42") (name "Net-(J2-PadB5)") (class "Default")
      (node (ref "J2") (pin "B5") (pinfunction "B5_B5") (pintype "bidirectional"))
      (node (ref "R2-USB") (pin "1") (pinfunction "1_1") (pintype "passive"))
    )
    (net (code "43") (name "Net-(U5-PROG)") (class "Default")
      (node (ref "R2_BAT") (pin "2") (pinfunction "2_2") (pintype "passive"))
      (node (ref "U5") (pin "5") (pinfunction "PROG_5") (pintype "input"))
    )
    (net (code "44") (name "Net-(U5-STAT)") (class "Default")
      (node (ref "R1_BAT") (pin "2") (pinfunction "2_2") (pintype "passive"))
      (node (ref "U5") (pin "1") (pinfunction "STAT_1") (pintype "output"))
    )
    (net (code "45") (name "PREVGH") (class "Default")
      (node (ref "D5") (pin "1") (pinfunction "K_1") (pintype "bidirectional"))
      (node (ref "EPD_C9") (pin "1") (pinfunction "1_1") (pintype "passive"))
      (node (ref "J1") (pin "21") (pinfunction "21_21") (pintype "bidirectional"))
    )
    (net (code "46") (name "PREVGL") (class "Default")
      (node (ref "D4") (pin "2") (pinfunction "A_2") (pintype "bidirectional"))
      (node (ref "EPD_C11") (pin "1") (pinfunction "1_1") (pintype "passive"))
      (node (ref "J1") (pin "23") (pinfunction "23_23") (pintype "bidirectional"))
    )
    (net (code "47") (name "RESE") (class "Default")
      (node (ref "J1") (pin "3") (pinfunction "3_3") (pintype "bidirectional"))
      (node (ref "Q3") (pin "2") (pinfunction "S_2") (pintype "bidirectional"))
      (node (ref "R3") (pin "2") (pinfunction "2_2") (pintype "passive"))
    )
    (net (code "48") (name "RESE'") (class "Default")
      (node (ref "R2") (pin "2") (pinfunction "2_2") (pintype "passive"))
      (node (ref "R3") (pin "1") (pinfunction "1_1") (pintype "passive"))
      (node (ref "SJ1") (pin "2") (pinfunction "2_2") (pintype "passive"))
    )
    (net (code "49") (name "RESET") (class "Default")
      (node (ref "C5") (pin "1") (pinfunction "1_1") (pintype "passive"))
      (node (ref "IC1") (pin "1") (pinfunction "VOUT_1") (pintype "bidirectional"))
      (node (ref "RESET_BUTTON") (pin "3") (pinfunction "3_3") (pintype "passive"))
      (node (ref "RESET_BUTTON") (pin "4") (pinfunction "4_4") (pintype "passive"))
      (node (ref "R_RESET") (pin "1") (pinfunction "1_1") (pintype "passive"))
      (node (ref "U2") (pin "3") (pinfunction "EN_3") (pintype "input"))
    )
    (net (code "50") (name "RTC_RST") (class "Default")
      (node (ref "U2") (pin "16") (pinfunction "IO18_16") (pintype "bidirectional"))
      (node (ref "U3") (pin "4") (pinfunction "~{RST}_4") (pintype "input"))
    )
    (net (code "51") (name "RX") (class "Default")
      (node (ref "TP2") (pin "TP") (pinfunction "TP_TP") (pintype "input"))
      (node (ref "U2") (pin "24") (pinfunction "RXD0/GPIO17_24") (pintype "bidirectional"))
    )
    (net (code "52") (name "SCK") (class "Default")
      (node (ref "J1") (pin "13") (pinfunction "13_13") (pintype "bidirectional"))
      (node (ref "J4") (pin "P5") (pinfunction "CLK_P5") (pintype "bidirectional"))
      (node (ref "TP8") (pin "TP") (pinfunction "TP_TP") (pintype "input"))
      (node (ref "U1") (pin "6") (pinfunction "CLK_6") (pintype "input"))
      (node (ref "U2") (pin "6") (pinfunction "IO6_6") (pintype "bidirectional"))
    )
    (net (code "53") (name "SCL") (class "Default")
      (node (ref "J3") (pin "4") (pinfunction "4_4") (pintype "passive"))
      (node (ref "R2-PINH") (pin "2") (pinfunction "2_2") (pintype "passive"))
      (node (ref "SENSOR2") (pin "4") (pinfunction "SCK_4") (pintype "input"))
      (node (ref "U2") (pin "20") (pinfunction "IO22_20") (pintype "bidirectional"))
      (node (ref "U3") (pin "16") (pinfunction "SCL_16") (pintype "input"))
      (node (ref "U4") (pin "7") (pinfunction "SCL_7") (pintype "input"))
    )
    (net (code "54") (name "SDA") (class "Default")
      (node (ref "J3") (pin "3") (pinfunction "3_3") (pintype "passive"))
      (node (ref "R1_PINH") (pin "2") (pinfunction "2_2") (pintype "passive"))
      (node (ref "SENSOR2") (pin "3") (pinfunction "SDI_3") (pintype "bidirectional"))
      (node (ref "U2") (pin "19") (pinfunction "IO21_19") (pintype "bidirectional"))
      (node (ref "U3") (pin "15") (pinfunction "SDA_15") (pintype "bidirectional"))
      (node (ref "U4") (pin "8") (pinfunction "SDA_8") (pintype "bidirectional"))
    )
    (net (code "55") (name "SRC") (class "Default")
      (node (ref "C4") (pin "2") (pinfunction "2_2") (pintype "passive"))
      (node (ref "D5") (pin "2") (pinfunction "A_2") (pintype "bidirectional"))
      (node (ref "L1") (pin "1") (pinfunction "1_1") (pintype "passive"))
      (node (ref "Q3") (pin "3") (pinfunction "D_3") (pintype "bidirectional"))
    )
    (net (code "56") (name "SS_SD") (class "Default")
      (node (ref "J4") (pin "P2") (pinfunction "CD/DAT3_P2") (pintype "bidirectional"))
      (node (ref "U2") (pin "4") (pinfunction "IO4_4") (pintype "bidirectional"))
    )
    (net (code "57") (name "TX") (class "Default")
      (node (ref "TP1") (pin "TP") (pinfunction "TP_TP") (pintype "input"))
      (node (ref "U2") (pin "25") (pinfunction "TXD0/GPIO16_25") (pintype "bidirectional"))
    )
    (net (code "58") (name "USB_D+") (class "Default")
      (node (ref "D1") (pin "1") (pinfunction "I/O1_1_1") (pintype "bidirectional"))
      (node (ref "U2") (pin "14") (pinfunction "IO13_14") (pintype "bidirectional"))
    )
    (net (code "59") (name "USB_D-") (class "Default")
      (node (ref "D1") (pin "3") (pinfunction "I/O2_1_3") (pintype "bidirectional"))
      (node (ref "U2") (pin "13") (pinfunction "IO12_13") (pintype "bidirectional"))
    )
    (net (code "60") (name "VBAT") (class "Default")
      (node (ref "C2_BAT") (pin "1") (pinfunction "1_1") (pintype "passive"))
      (node (ref "Q1") (pin "3") (pinfunction "D_3") (pintype "bidirectional"))
      (node (ref "TP3") (pin "TP") (pinfunction "TP_TP") (pintype "input"))
      (node (ref "U4") (pin "2") (pinfunction "CELL_2") (pintype "power_in"))
      (node (ref "U4") (pin "3") (pinfunction "VDD_3") (pintype "power_in"))
      (node (ref "U5") (pin "3") (pinfunction "VBAT_3") (pintype "power_in"))
    )
    (net (code "61") (name "VBUS") (class "Default")
      (node (ref "C1_BAT") (pin "1") (pinfunction "1_1") (pintype "passive"))
      (node (ref "C4_USB") (pin "1") (pinfunction "1_1") (pintype "passive"))
      (node (ref "C5_USB") (pin "1") (pinfunction "1_1") (pintype "passive"))
      (node (ref "CHG_LED") (pin "A") (pinfunction "A_A") (pintype "passive"))
      (node (ref "D1") (pin "5") (pinfunction "VBUS_5") (pintype "bidirectional"))
      (node (ref "D2") (pin "2") (pinfunction "ANODE_2") (pintype "bidirectional"))
      (node (ref "PFMF.050.1") (pin "2") (pinfunction "2_2") (pintype "passive"))
      (node (ref "Q1") (pin "1") (pinfunction "G_1") (pintype "bidirectional"))
      (node (ref "R1_PWRUSB") (pin "2") (pinfunction "2_2") (pintype "passive"))
      (node (ref "TP14") (pin "TP") (pinfunction "TP_TP") (pintype "input"))
      (node (ref "U5") (pin "4") (pinfunction "VIN_4") (pintype "power_in"))
    )
    (net (code "62") (name "VRTC") (class "Default")
      (node (ref "C10_SUPERCAP") (pin "2") (pinfunction "2_2") (pintype "passive"))
      (node (ref "C8") (pin "1") (pinfunction "1_1") (pintype "passive"))
      (node (ref "R_CAPACITOR") (pin "2") (pinfunction "2_2") (pintype "passive"))
      (node (ref "U3") (pin "14") (pinfunction "VBAT_14") (pintype "power_in"))
    )
    (net (code "63") (name "VUSB") (class "Default")
      (node (ref "J2") (pin "A4") (pinfunction "A4_A4") (pintype "bidirectional"))
      (node (ref "J2") (pin "A9") (pinfunction "A9_A9") (pintype "bidirectional"))
      (node (ref "J2") (pin "B4") (pinfunction "B4_B4") (pintype "bidirectional"))
      (node (ref "J2") (pin "B9") (pinfunction "B9_B9") (pintype "bidirectional"))
      (node (ref "PFMF.050.1") (pin "1") (pinfunction "1_1") (pintype "passive"))
    )
    (net (code "64") (name "unconnected-(IC1-NC-Pad4)") (class "Default")
      (node (ref "IC1") (pin "4") (pinfunction "NC_4") (pintype "no_connect"))
    )
    (net (code "65") (name "unconnected-(IC4-NC-Pad4)") (class "Default")
      (node (ref "IC4") (pin "4") (pinfunction "NC_4") (pintype "no_connect"))
    )
    (net (code "66") (name "unconnected-(J1-Pad1)") (class "Default")
      (node (ref "J1") (pin "1") (pinfunction "1_1") (pintype "bidirectional"))
    )
    (net (code "67") (name "unconnected-(J1-Pad6)") (class "Default")
      (node (ref "J1") (pin "6") (pinfunction "6_6") (pintype "bidirectional"))
    )
    (net (code "68") (name "unconnected-(J1-Pad7)") (class "Default")
      (node (ref "J1") (pin "7") (pinfunction "7_7") (pintype "bidirectional"))
    )
    (net (code "69") (name "unconnected-(J1-PadMP1)") (class "Default")
      (node (ref "J1") (pin "MP1") (pinfunction "MP1_MP1") (pintype "bidirectional"))
    )
    (net (code "70") (name "unconnected-(J1-PadMP2)") (class "Default")
      (node (ref "J1") (pin "MP2") (pinfunction "MP2_MP2") (pintype "bidirectional"))
    )
    (net (code "71") (name "unconnected-(J2-PadA8)") (class "Default")
      (node (ref "J2") (pin "A8") (pinfunction "A8_A8") (pintype "bidirectional"))
    )
    (net (code "72") (name "unconnected-(J2-PadB8)") (class "Default")
      (node (ref "J2") (pin "B8") (pinfunction "B8_B8") (pintype "bidirectional"))
    )
    (net (code "73") (name "unconnected-(J4-DAT1-PadP8)") (class "Default")
      (node (ref "J4") (pin "P8") (pinfunction "DAT1_P8") (pintype "bidirectional"))
    )
    (net (code "74") (name "unconnected-(J4-DAT2-PadP1)") (class "Default")
      (node (ref "J4") (pin "P1") (pinfunction "DAT2_P1") (pintype "bidirectional"))
    )
    (net (code "75") (name "unconnected-(J4-DETECTION_1-PadS1)") (class "Default")
      (node (ref "J4") (pin "S1") (pinfunction "DETECTION_1_S1") (pintype "bidirectional"))
    )
    (net (code "76") (name "unconnected-(J4-DETECTION_2-PadS2)") (class "Default")
      (node (ref "J4") (pin "S2") (pinfunction "DETECTION_2_S2") (pintype "bidirectional"))
    )
    (net (code "77") (name "unconnected-(U2-NC-Pad22)") (class "Default")
      (node (ref "U2") (pin "22") (pinfunction "NC_22") (pintype "no_connect"))
    )
    (net (code "78") (name "unconnected-(U4-~{ALERT}-Pad5)") (class "Default")
      (node (ref "U4") (pin "5") (pinfunction "~{ALERT}_5") (pintype "output"))
    )
  )
)
